# AST2002.net
KiCad netlist of a schematic drawn in EAGLE
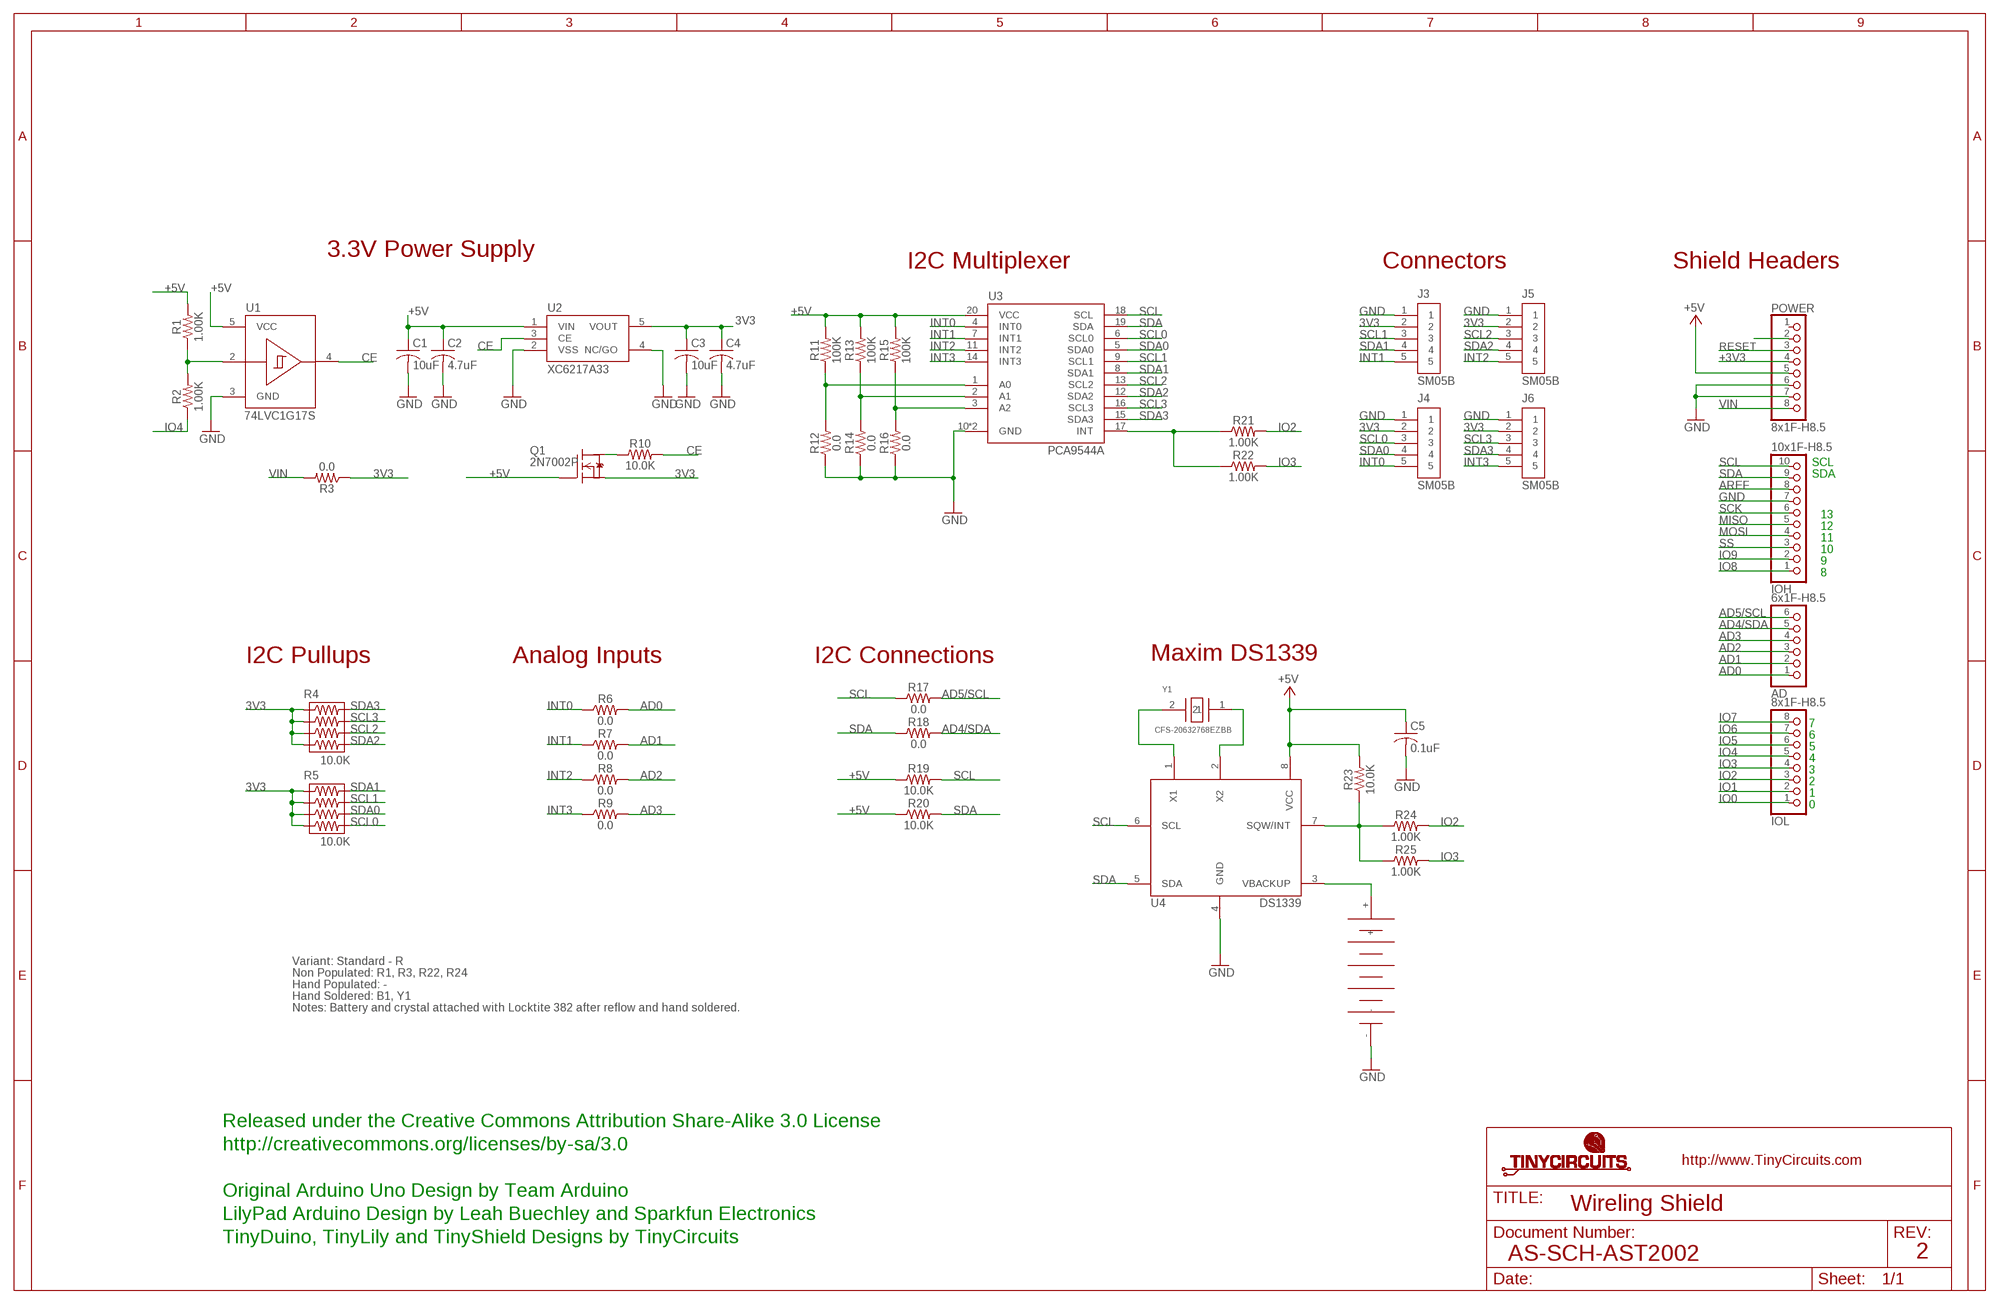
[diagram p0: schematic, sheet 1]

(export (version "E")
  (design (tool "Eeschema 10.0.6"))
  (components
    (comp (ref "AD")
      (value "6x1F-H8.5")
      (footprint "eagle-import:1X06")
      (libsource (lib "eagle-import") (part "PINHD-1X6"))
    )
    (comp (ref "B1")
      (value "ML-920S/DN")
      (footprint "eagle-import:ML-920S_DN")
      (fields (field (name "PARTNO") "AS-ITM-00182"))
      (libsource (lib "eagle-import") (part "AS-ITM-00182"))
    )
    (comp (ref "C1")
      (value "10uF")
      (footprint "eagle-import:C0603")
      (fields (field (name "PARTNO") "AS-ITM-00002") (field (name "PARTNO_1") "AS-ITM-00002"))
      (libsource (lib "eagle-import") (part "AS-ITM-00002"))
    )
    (comp (ref "C2")
      (value "4.7uF")
      (footprint "eagle-import:C0402")
      (fields (field (name "PARTNO") "AS-ITM-00242") (field (name "PARTNO_1") "AS-ITM-00242"))
      (libsource (lib "eagle-import") (part "AS-ITM-00242"))
    )
    (comp (ref "C3")
      (value "10uF")
      (footprint "eagle-import:C0603")
      (fields (field (name "PARTNO") "AS-ITM-00002"))
      (libsource (lib "eagle-import") (part "AS-ITM-00002"))
    )
    (comp (ref "C4")
      (value "4.7uF")
      (footprint "eagle-import:C0402")
      (fields (field (name "PARTNO") "AS-ITM-00242") (field (name "PARTNO_1") "AS-ITM-00242"))
      (libsource (lib "eagle-import") (part "AS-ITM-00242"))
    )
    (comp (ref "C5")
      (value "0.1uF")
      (footprint "eagle-import:C0402")
      (fields (field (name "PARTNO") "AS-ITM-00008"))
      (libsource (lib "eagle-import") (part "AS-ITM-00008"))
    )
    (comp (ref "IOH")
      (value "10x1F-H8.5")
      (footprint "eagle-import:1X10")
      (libsource (lib "eagle-import") (part "PINHD-1X10_ARD"))
    )
    (comp (ref "IOL")
      (value "8x1F-H8.5")
      (footprint "eagle-import:1X08")
      (libsource (lib "eagle-import") (part "PINHD-1X8"))
    )
    (comp (ref "J3")
      (value "SM05B")
      (footprint "eagle-import:JST_SH_5X1")
      (fields (field (name "PARTNO") "AS-ITM-00340"))
      (libsource (lib "eagle-import") (part "AS-ITM-00340"))
    )
    (comp (ref "J4")
      (value "SM05B")
      (footprint "eagle-import:JST_SH_5X1")
      (fields (field (name "PARTNO") "AS-ITM-00340"))
      (libsource (lib "eagle-import") (part "AS-ITM-00340"))
    )
    (comp (ref "J5")
      (value "SM05B")
      (footprint "eagle-import:JST_SH_5X1")
      (fields (field (name "PARTNO") "AS-ITM-00340"))
      (libsource (lib "eagle-import") (part "AS-ITM-00340"))
    )
    (comp (ref "J6")
      (value "SM05B")
      (footprint "eagle-import:JST_SH_5X1")
      (fields (field (name "PARTNO") "AS-ITM-00340"))
      (libsource (lib "eagle-import") (part "AS-ITM-00340"))
    )
    (comp (ref "POWER")
      (value "8x1F-H8.5")
      (footprint "eagle-import:1X08")
      (libsource (lib "eagle-import") (part "PINHD-1X8"))
    )
    (comp (ref "Q1")
      (value "2N7002P")
      (footprint "eagle-import:SOT-416")
      (fields (field (name "PARTNO") "AS-ITM-00110") (field (name "PARTNO_1") "AS-ITM-00110"))
      (libsource (lib "eagle-import") (part "AS-ITM-00110"))
    )
    (comp (ref "R1")
      (value "1.00K")
      (footprint "eagle-import:0402")
      (fields (field (name "PARTNO") "AS-ITM-00003") (field (name "PARTNO_1") "AS-ITM-00003"))
      (libsource (lib "eagle-import") (part "AS-ITM-00003"))
    )
    (comp (ref "R2")
      (value "1.00K")
      (footprint "eagle-import:0402")
      (fields (field (name "PARTNO") "AS-ITM-00003") (field (name "PARTNO_1") "AS-ITM-00003"))
      (libsource (lib "eagle-import") (part "AS-ITM-00003"))
    )
    (comp (ref "R3")
      (value "0.0")
      (footprint "eagle-import:0402")
      (fields (field (name "PARTNO") "AS-ITM-00076") (field (name "PARTNO_1") "AS-ITM-00076"))
      (libsource (lib "eagle-import") (part "AS-ITM-00076"))
    )
    (comp (ref "R4")
      (value "10.0K")
      (footprint "eagle-import:0402RPACK")
      (fields (field (name "PARTNO") "AS-ITM-00520") (field (name "PARTNO_1") "AS-ITM-00520"))
      (libsource (lib "eagle-import") (part "AS-ITM-00520"))
    )
    (comp (ref "R5")
      (value "10.0K")
      (footprint "eagle-import:0402RPACK")
      (fields (field (name "PARTNO") "AS-ITM-00520") (field (name "PARTNO_1") "AS-ITM-00520"))
      (libsource (lib "eagle-import") (part "AS-ITM-00520"))
    )
    (comp (ref "R6")
      (value "0.0")
      (footprint "eagle-import:0402")
      (fields (field (name "PARTNO") "AS-ITM-00076"))
      (libsource (lib "eagle-import") (part "AS-ITM-00076"))
    )
    (comp (ref "R7")
      (value "0.0")
      (footprint "eagle-import:0402")
      (fields (field (name "PARTNO") "AS-ITM-00076"))
      (libsource (lib "eagle-import") (part "AS-ITM-00076"))
    )
    (comp (ref "R8")
      (value "0.0")
      (footprint "eagle-import:0402")
      (fields (field (name "PARTNO") "AS-ITM-00076"))
      (libsource (lib "eagle-import") (part "AS-ITM-00076"))
    )
    (comp (ref "R9")
      (value "0.0")
      (footprint "eagle-import:0402")
      (fields (field (name "PARTNO") "AS-ITM-00076"))
      (libsource (lib "eagle-import") (part "AS-ITM-00076"))
    )
    (comp (ref "R10")
      (value "10.0K")
      (footprint "eagle-import:0402")
      (fields (field (name "PARTNO") "AS-ITM-00032") (field (name "PARTNO_1") "AS-ITM-00032"))
      (libsource (lib "eagle-import") (part "AS-ITM-00032"))
    )
    (comp (ref "R11")
      (value "100K")
      (footprint "eagle-import:0402")
      (fields (field (name "PARTNO") "AS-ITM-00004") (field (name "PARTNO_1") "AS-ITM-00004"))
      (libsource (lib "eagle-import") (part "AS-ITM-00004"))
    )
    (comp (ref "R12")
      (value "0.0")
      (footprint "eagle-import:0402")
      (fields (field (name "PARTNO") "AS-ITM-00076") (field (name "PARTNO_1") "AS-ITM-00076"))
      (libsource (lib "eagle-import") (part "AS-ITM-00076"))
    )
    (comp (ref "R13")
      (value "100K")
      (footprint "eagle-import:0402")
      (fields (field (name "PARTNO") "AS-ITM-00004") (field (name "PARTNO_1") "AS-ITM-00004"))
      (libsource (lib "eagle-import") (part "AS-ITM-00004"))
    )
    (comp (ref "R14")
      (value "0.0")
      (footprint "eagle-import:0402")
      (fields (field (name "PARTNO") "AS-ITM-00076") (field (name "PARTNO_1") "AS-ITM-00076"))
      (libsource (lib "eagle-import") (part "AS-ITM-00076"))
    )
    (comp (ref "R15")
      (value "100K")
      (footprint "eagle-import:0402")
      (fields (field (name "PARTNO") "AS-ITM-00004") (field (name "PARTNO_1") "AS-ITM-00004"))
      (libsource (lib "eagle-import") (part "AS-ITM-00004"))
    )
    (comp (ref "R16")
      (value "0.0")
      (footprint "eagle-import:0402")
      (fields (field (name "PARTNO") "AS-ITM-00076") (field (name "PARTNO_1") "AS-ITM-00076"))
      (libsource (lib "eagle-import") (part "AS-ITM-00076"))
    )
    (comp (ref "R17")
      (value "0.0")
      (footprint "eagle-import:0402")
      (fields (field (name "PARTNO") "AS-ITM-00076"))
      (libsource (lib "eagle-import") (part "AS-ITM-00076"))
    )
    (comp (ref "R18")
      (value "0.0")
      (footprint "eagle-import:0402")
      (fields (field (name "PARTNO") "AS-ITM-00076"))
      (libsource (lib "eagle-import") (part "AS-ITM-00076"))
    )
    (comp (ref "R19")
      (value "10.0K")
      (footprint "eagle-import:0402")
      (fields (field (name "PARTNO") "AS-ITM-00032"))
      (libsource (lib "eagle-import") (part "AS-ITM-00032"))
    )
    (comp (ref "R20")
      (value "10.0K")
      (footprint "eagle-import:0402")
      (fields (field (name "PARTNO") "AS-ITM-00032"))
      (libsource (lib "eagle-import") (part "AS-ITM-00032"))
    )
    (comp (ref "R21")
      (value "1.00K")
      (footprint "eagle-import:0402")
      (fields (field (name "PARTNO") "AS-ITM-00003"))
      (libsource (lib "eagle-import") (part "AS-ITM-00003"))
    )
    (comp (ref "R22")
      (value "1.00K")
      (footprint "eagle-import:0402")
      (fields (field (name "PARTNO") "AS-ITM-00003"))
      (libsource (lib "eagle-import") (part "AS-ITM-00003"))
    )
    (comp (ref "R23")
      (value "10.0K")
      (footprint "eagle-import:0402")
      (fields (field (name "PARTNO") "AS-ITM-00032") (field (name "PARTNO_1") "AS-ITM-00032"))
      (libsource (lib "eagle-import") (part "AS-ITM-00032"))
    )
    (comp (ref "R24")
      (value "1.00K")
      (footprint "eagle-import:0402")
      (fields (field (name "PARTNO") "AS-ITM-00003") (field (name "PARTNO_1") "AS-ITM-00003"))
      (libsource (lib "eagle-import") (part "AS-ITM-00003"))
    )
    (comp (ref "R25")
      (value "1.00K")
      (footprint "eagle-import:0402")
      (fields (field (name "PARTNO") "AS-ITM-00003") (field (name "PARTNO_1") "AS-ITM-00003"))
      (libsource (lib "eagle-import") (part "AS-ITM-00003"))
    )
    (comp (ref "U1")
      (value "74LVC1G17S")
      (footprint "eagle-import:SOT-353")
      (fields (field (name "PARTNO") "AS-ITM-00382"))
      (libsource (lib "eagle-import") (part "AS-ITM-00382"))
    )
    (comp (ref "U2")
      (value "XC6217A33")
      (footprint "eagle-import:SOT-25")
      (fields (field (name "PARTNO") "AS-ITM-00249") (field (name "PARTNO_1") "AS-ITM-00249"))
      (libsource (lib "eagle-import") (part "AS-ITM-00249"))
    )
    (comp (ref "U3")
      (value "PCA9544A")
      (footprint "eagle-import:VQFN-20_4.5X3.5")
      (fields (field (name "PARTNO") "AS-ITM-00342"))
      (libsource (lib "eagle-import") (part "AS-ITM-00342"))
    )
    (comp (ref "U4")
      (value "DS1339")
      (footprint "eagle-import:8-USOP")
      (fields (field (name "PARTNO") "AS-ITM-00181"))
      (libsource (lib "eagle-import") (part "AS-ITM-00181"))
    )
    (comp (ref "Y1")
      (value "CFS-20632768EZBB")
      (footprint "eagle-import:CRYSTAL_1.9MM_TH")
      (fields (field (name "PARTNO") "AS-ITM-00348"))
      (libsource (lib "eagle-import") (part "AS-ITM-00348"))
    )
  )
  (nets
    (net (code "1") (name "+5V") (class "Default")
      (node (ref "C1") (pin "1") (pinfunction "1_1") (pintype "passive"))
      (node (ref "C2") (pin "1") (pinfunction "1_1") (pintype "passive"))
      (node (ref "C5") (pin "1") (pinfunction "1_1") (pintype "passive"))
      (node (ref "POWER") (pin "5") (pinfunction "5_5") (pintype "passive"))
      (node (ref "Q1") (pin "1") (pinfunction "G_1") (pintype "passive"))
      (node (ref "R1") (pin "2") (pinfunction "2_2") (pintype "passive"))
      (node (ref "R11") (pin "2") (pinfunction "2_2") (pintype "passive"))
      (node (ref "R13") (pin "2") (pinfunction "2_2") (pintype "passive"))
      (node (ref "R15") (pin "2") (pinfunction "2_2") (pintype "passive"))
      (node (ref "R19") (pin "1") (pinfunction "1_1") (pintype "passive"))
      (node (ref "R20") (pin "1") (pinfunction "1_1") (pintype "passive"))
      (node (ref "R23") (pin "2") (pinfunction "2_2") (pintype "passive"))
      (node (ref "U1") (pin "5") (pinfunction "VCC_5") (pintype "bidirectional"))
      (node (ref "U2") (pin "1") (pinfunction "VIN_1") (pintype "bidirectional"))
      (node (ref "U3") (pin "20") (pinfunction "VCC_20") (pintype "bidirectional"))
      (node (ref "U4") (pin "8") (pinfunction "VCC_8") (pintype "bidirectional"))
    )
    (net (code "2") (name "/+3V3") (class "Default")
      (node (ref "POWER") (pin "4") (pinfunction "4_4") (pintype "passive"))
    )
    (net (code "3") (name "/3V3") (class "Default")
      (node (ref "C3") (pin "1") (pinfunction "1_1") (pintype "passive"))
      (node (ref "C4") (pin "1") (pinfunction "1_1") (pintype "passive"))
      (node (ref "J3") (pin "2") (pinfunction "2_2") (pintype "bidirectional"))
      (node (ref "J4") (pin "2") (pinfunction "2_2") (pintype "bidirectional"))
      (node (ref "J5") (pin "2") (pinfunction "2_2") (pintype "bidirectional"))
      (node (ref "J6") (pin "2") (pinfunction "2_2") (pintype "bidirectional"))
      (node (ref "Q1") (pin "2") (pinfunction "S_2") (pintype "passive"))
      (node (ref "R3") (pin "1") (pinfunction "1_1") (pintype "passive"))
      (node (ref "R4") (pin "1") (pinfunction "1_1") (pintype "passive"))
      (node (ref "R4") (pin "3") (pinfunction "3_3") (pintype "passive"))
      (node (ref "R4") (pin "5") (pinfunction "5_5") (pintype "passive"))
      (node (ref "R4") (pin "7") (pinfunction "7_7") (pintype "passive"))
      (node (ref "R5") (pin "1") (pinfunction "1_1") (pintype "passive"))
      (node (ref "R5") (pin "3") (pinfunction "3_3") (pintype "passive"))
      (node (ref "R5") (pin "5") (pinfunction "5_5") (pintype "passive"))
      (node (ref "R5") (pin "7") (pinfunction "7_7") (pintype "passive"))
      (node (ref "U2") (pin "5") (pinfunction "VOUT_5") (pintype "bidirectional"))
    )
    (net (code "4") (name "/AD0") (class "Default")
      (node (ref "AD") (pin "1") (pinfunction "1_1") (pintype "passive"))
      (node (ref "R6") (pin "2") (pinfunction "2_2") (pintype "passive"))
    )
    (net (code "5") (name "/AD1") (class "Default")
      (node (ref "AD") (pin "2") (pinfunction "2_2") (pintype "passive"))
      (node (ref "R7") (pin "2") (pinfunction "2_2") (pintype "passive"))
    )
    (net (code "6") (name "/AD2") (class "Default")
      (node (ref "AD") (pin "3") (pinfunction "3_3") (pintype "passive"))
      (node (ref "R8") (pin "2") (pinfunction "2_2") (pintype "passive"))
    )
    (net (code "7") (name "/AD3") (class "Default")
      (node (ref "AD") (pin "4") (pinfunction "4_4") (pintype "passive"))
      (node (ref "R9") (pin "2") (pinfunction "2_2") (pintype "passive"))
    )
    (net (code "8") (name "/AD4{slash}SDA") (class "Default")
      (node (ref "AD") (pin "5") (pinfunction "5_5") (pintype "passive"))
      (node (ref "R18") (pin "2") (pinfunction "2_2") (pintype "passive"))
    )
    (net (code "9") (name "/AD5{slash}SCL") (class "Default")
      (node (ref "AD") (pin "6") (pinfunction "6_6") (pintype "passive"))
      (node (ref "R17") (pin "2") (pinfunction "2_2") (pintype "passive"))
    )
    (net (code "10") (name "/AREF") (class "Default")
      (node (ref "IOH") (pin "8") (pinfunction "8_8") (pintype "passive"))
    )
    (net (code "11") (name "/CE") (class "Default")
      (node (ref "R10") (pin "2") (pinfunction "2_2") (pintype "passive"))
      (node (ref "U1") (pin "4") (pinfunction "Y_4") (pintype "bidirectional"))
      (node (ref "U2") (pin "3") (pinfunction "CE_3") (pintype "bidirectional"))
    )
    (net (code "12") (name "/INT0") (class "Default")
      (node (ref "J4") (pin "5") (pinfunction "5_5") (pintype "bidirectional"))
      (node (ref "R6") (pin "1") (pinfunction "1_1") (pintype "passive"))
      (node (ref "U3") (pin "4") (pinfunction "INT0_4") (pintype "bidirectional"))
    )
    (net (code "13") (name "/INT1") (class "Default")
      (node (ref "J3") (pin "5") (pinfunction "5_5") (pintype "bidirectional"))
      (node (ref "R7") (pin "1") (pinfunction "1_1") (pintype "passive"))
      (node (ref "U3") (pin "7") (pinfunction "INT1_7") (pintype "bidirectional"))
    )
    (net (code "14") (name "/INT2") (class "Default")
      (node (ref "J5") (pin "5") (pinfunction "5_5") (pintype "bidirectional"))
      (node (ref "R8") (pin "1") (pinfunction "1_1") (pintype "passive"))
      (node (ref "U3") (pin "11") (pinfunction "INT2_11") (pintype "bidirectional"))
    )
    (net (code "15") (name "/INT3") (class "Default")
      (node (ref "J6") (pin "5") (pinfunction "5_5") (pintype "bidirectional"))
      (node (ref "R9") (pin "1") (pinfunction "1_1") (pintype "passive"))
      (node (ref "U3") (pin "14") (pinfunction "INT3_14") (pintype "bidirectional"))
    )
    (net (code "16") (name "/IO0") (class "Default")
      (node (ref "IOL") (pin "1") (pinfunction "1_1") (pintype "passive"))
    )
    (net (code "17") (name "/IO1") (class "Default")
      (node (ref "IOL") (pin "2") (pinfunction "2_2") (pintype "passive"))
    )
    (net (code "18") (name "/IO2") (class "Default")
      (node (ref "IOL") (pin "3") (pinfunction "3_3") (pintype "passive"))
      (node (ref "R21") (pin "2") (pinfunction "2_2") (pintype "passive"))
      (node (ref "R24") (pin "2") (pinfunction "2_2") (pintype "passive"))
    )
    (net (code "19") (name "/IO3") (class "Default")
      (node (ref "IOL") (pin "4") (pinfunction "4_4") (pintype "passive"))
      (node (ref "R22") (pin "2") (pinfunction "2_2") (pintype "passive"))
      (node (ref "R25") (pin "2") (pinfunction "2_2") (pintype "passive"))
    )
    (net (code "20") (name "/IO4") (class "Default")
      (node (ref "IOL") (pin "5") (pinfunction "5_5") (pintype "passive"))
      (node (ref "R2") (pin "1") (pinfunction "1_1") (pintype "passive"))
    )
    (net (code "21") (name "/IO5") (class "Default")
      (node (ref "IOL") (pin "6") (pinfunction "6_6") (pintype "passive"))
    )
    (net (code "22") (name "/IO6") (class "Default")
      (node (ref "IOL") (pin "7") (pinfunction "7_7") (pintype "passive"))
    )
    (net (code "23") (name "/IO7") (class "Default")
      (node (ref "IOL") (pin "8") (pinfunction "8_8") (pintype "passive"))
    )
    (net (code "24") (name "/IO8") (class "Default")
      (node (ref "IOH") (pin "1") (pinfunction "1_1") (pintype "passive"))
    )
    (net (code "25") (name "/IO9") (class "Default")
      (node (ref "IOH") (pin "2") (pinfunction "2_2") (pintype "passive"))
    )
    (net (code "26") (name "/MISO") (class "Default")
      (node (ref "IOH") (pin "5") (pinfunction "5_5") (pintype "passive"))
    )
    (net (code "27") (name "/MOSI") (class "Default")
      (node (ref "IOH") (pin "4") (pinfunction "4_4") (pintype "passive"))
    )
    (net (code "28") (name "/RESET") (class "Default")
      (node (ref "POWER") (pin "3") (pinfunction "3_3") (pintype "passive"))
    )
    (net (code "29") (name "/SCK") (class "Default")
      (node (ref "IOH") (pin "6") (pinfunction "6_6") (pintype "passive"))
    )
    (net (code "30") (name "/SCL") (class "Default")
      (node (ref "IOH") (pin "10") (pinfunction "10_10") (pintype "passive"))
      (node (ref "R17") (pin "1") (pinfunction "1_1") (pintype "passive"))
      (node (ref "R19") (pin "2") (pinfunction "2_2") (pintype "passive"))
      (node (ref "U3") (pin "18") (pinfunction "SCL_18") (pintype "bidirectional"))
      (node (ref "U4") (pin "6") (pinfunction "SCL_6") (pintype "bidirectional"))
    )
    (net (code "31") (name "/SCL0") (class "Default")
      (node (ref "J4") (pin "3") (pinfunction "3_3") (pintype "bidirectional"))
      (node (ref "R5") (pin "8") (pinfunction "8_8") (pintype "passive"))
      (node (ref "U3") (pin "6") (pinfunction "SCL0_6") (pintype "bidirectional"))
    )
    (net (code "32") (name "/SCL1") (class "Default")
      (node (ref "J3") (pin "3") (pinfunction "3_3") (pintype "bidirectional"))
      (node (ref "R5") (pin "4") (pinfunction "4_4") (pintype "passive"))
      (node (ref "U3") (pin "9") (pinfunction "SCL1_9") (pintype "bidirectional"))
    )
    (net (code "33") (name "/SCL2") (class "Default")
      (node (ref "J5") (pin "3") (pinfunction "3_3") (pintype "bidirectional"))
      (node (ref "R4") (pin "6") (pinfunction "6_6") (pintype "passive"))
      (node (ref "U3") (pin "13") (pinfunction "SCL2_13") (pintype "bidirectional"))
    )
    (net (code "34") (name "/SCL3") (class "Default")
      (node (ref "J6") (pin "3") (pinfunction "3_3") (pintype "bidirectional"))
      (node (ref "R4") (pin "4") (pinfunction "4_4") (pintype "passive"))
      (node (ref "U3") (pin "16") (pinfunction "SCL3_16") (pintype "bidirectional"))
    )
    (net (code "35") (name "/SDA") (class "Default")
      (node (ref "IOH") (pin "9") (pinfunction "9_9") (pintype "passive"))
      (node (ref "R18") (pin "1") (pinfunction "1_1") (pintype "passive"))
      (node (ref "R20") (pin "2") (pinfunction "2_2") (pintype "passive"))
      (node (ref "U3") (pin "19") (pinfunction "SDA_19") (pintype "bidirectional"))
      (node (ref "U4") (pin "5") (pinfunction "SDA_5") (pintype "bidirectional"))
    )
    (net (code "36") (name "/SDA0") (class "Default")
      (node (ref "J4") (pin "4") (pinfunction "4_4") (pintype "bidirectional"))
      (node (ref "R5") (pin "6") (pinfunction "6_6") (pintype "passive"))
      (node (ref "U3") (pin "5") (pinfunction "SDA0_5") (pintype "bidirectional"))
    )
    (net (code "37") (name "/SDA1") (class "Default")
      (node (ref "J3") (pin "4") (pinfunction "4_4") (pintype "bidirectional"))
      (node (ref "R5") (pin "2") (pinfunction "2_2") (pintype "passive"))
      (node (ref "U3") (pin "8") (pinfunction "SDA1_8") (pintype "bidirectional"))
    )
    (net (code "38") (name "/SDA2") (class "Default")
      (node (ref "J5") (pin "4") (pinfunction "4_4") (pintype "bidirectional"))
      (node (ref "R4") (pin "8") (pinfunction "8_8") (pintype "passive"))
      (node (ref "U3") (pin "12") (pinfunction "SDA2_12") (pintype "bidirectional"))
    )
    (net (code "39") (name "/SDA3") (class "Default")
      (node (ref "J6") (pin "4") (pinfunction "4_4") (pintype "bidirectional"))
      (node (ref "R4") (pin "2") (pinfunction "2_2") (pintype "passive"))
      (node (ref "U3") (pin "15") (pinfunction "SDA3_15") (pintype "bidirectional"))
    )
    (net (code "40") (name "/SS") (class "Default")
      (node (ref "IOH") (pin "3") (pinfunction "3_3") (pintype "passive"))
    )
    (net (code "41") (name "/VIN") (class "Default")
      (node (ref "POWER") (pin "8") (pinfunction "8_8") (pintype "passive"))
      (node (ref "R3") (pin "2") (pinfunction "2_2") (pintype "passive"))
    )
    (net (code "42") (name "GND") (class "Default")
      (node (ref "B1") (pin "-") (pinfunction "-_-") (pintype "bidirectional"))
      (node (ref "C1") (pin "2") (pinfunction "2_2") (pintype "passive"))
      (node (ref "C2") (pin "2") (pinfunction "2_2") (pintype "passive"))
      (node (ref "C3") (pin "2") (pinfunction "2_2") (pintype "passive"))
      (node (ref "C4") (pin "2") (pinfunction "2_2") (pintype "passive"))
      (node (ref "C5") (pin "2") (pinfunction "2_2") (pintype "passive"))
      (node (ref "IOH") (pin "7") (pinfunction "7_7") (pintype "passive"))
      (node (ref "J3") (pin "1") (pinfunction "1_1") (pintype "bidirectional"))
      (node (ref "J4") (pin "1") (pinfunction "1_1") (pintype "bidirectional"))
      (node (ref "J5") (pin "1") (pinfunction "1_1") (pintype "bidirectional"))
      (node (ref "J6") (pin "1") (pinfunction "1_1") (pintype "bidirectional"))
      (node (ref "POWER") (pin "6") (pinfunction "6_6") (pintype "passive"))
      (node (ref "POWER") (pin "7") (pinfunction "7_7") (pintype "passive"))
      (node (ref "R12") (pin "1") (pinfunction "1_1") (pintype "passive"))
      (node (ref "R14") (pin "1") (pinfunction "1_1") (pintype "passive"))
      (node (ref "R16") (pin "1") (pinfunction "1_1") (pintype "passive"))
      (node (ref "U1") (pin "3") (pinfunction "GND_3") (pintype "bidirectional"))
      (node (ref "U2") (pin "2") (pinfunction "VSS_2") (pintype "power_in"))
      (node (ref "U2") (pin "4") (pinfunction "NC/GO_4") (pintype "bidirectional"))
      (node (ref "U3") (pin "10") (pinfunction "GND_10") (pintype "bidirectional"))
      (node (ref "U3") (pin "PAD") (pinfunction "GND_PAD") (pintype "bidirectional"))
      (node (ref "U4") (pin "4") (pinfunction "GND_4") (pintype "bidirectional"))
    )
    (net (code "43") (name "Net-(Q1-D)") (class "Default")
      (node (ref "Q1") (pin "3") (pinfunction "D_3") (pintype "passive"))
      (node (ref "R10") (pin "1") (pinfunction "1_1") (pintype "passive"))
    )
    (net (code "44") (name "Net-(U1-A)") (class "Default")
      (node (ref "R1") (pin "1") (pinfunction "1_1") (pintype "passive"))
      (node (ref "R2") (pin "2") (pinfunction "2_2") (pintype "passive"))
      (node (ref "U1") (pin "2") (pinfunction "A_2") (pintype "bidirectional"))
    )
    (net (code "45") (name "Net-(U3-A0)") (class "Default")
      (node (ref "R11") (pin "1") (pinfunction "1_1") (pintype "passive"))
      (node (ref "R12") (pin "2") (pinfunction "2_2") (pintype "passive"))
      (node (ref "U3") (pin "1") (pinfunction "A0_1") (pintype "bidirectional"))
    )
    (net (code "46") (name "Net-(U3-A1)") (class "Default")
      (node (ref "R13") (pin "1") (pinfunction "1_1") (pintype "passive"))
      (node (ref "R14") (pin "2") (pinfunction "2_2") (pintype "passive"))
      (node (ref "U3") (pin "2") (pinfunction "A1_2") (pintype "bidirectional"))
    )
    (net (code "47") (name "Net-(U3-A2)") (class "Default")
      (node (ref "R15") (pin "1") (pinfunction "1_1") (pintype "passive"))
      (node (ref "R16") (pin "2") (pinfunction "2_2") (pintype "passive"))
      (node (ref "U3") (pin "3") (pinfunction "A2_3") (pintype "bidirectional"))
    )
    (net (code "48") (name "Net-(U3-INT)") (class "Default")
      (node (ref "R21") (pin "1") (pinfunction "1_1") (pintype "passive"))
      (node (ref "R22") (pin "1") (pinfunction "1_1") (pintype "passive"))
      (node (ref "U3") (pin "17") (pinfunction "INT_17") (pintype "bidirectional"))
    )
    (net (code "49") (name "Net-(U4-SQW{slash}INT)") (class "Default")
      (node (ref "R23") (pin "1") (pinfunction "1_1") (pintype "passive"))
      (node (ref "R24") (pin "1") (pinfunction "1_1") (pintype "passive"))
      (node (ref "R25") (pin "1") (pinfunction "1_1") (pintype "passive"))
      (node (ref "U4") (pin "7") (pinfunction "SQW/INT_7") (pintype "bidirectional"))
    )
    (net (code "50") (name "Net-(U4-VBACKUP)") (class "Default")
      (node (ref "B1") (pin "+") (pinfunction "+_+") (pintype "bidirectional"))
      (node (ref "U4") (pin "3") (pinfunction "VBACKUP_3") (pintype "bidirectional"))
    )
    (net (code "51") (name "Net-(U4-X1)") (class "Default")
      (node (ref "U4") (pin "1") (pinfunction "X1_1") (pintype "bidirectional"))
      (node (ref "Y1") (pin "2") (pinfunction "1_2") (pintype "bidirectional"))
    )
    (net (code "52") (name "Net-(U4-X2)") (class "Default")
      (node (ref "U4") (pin "2") (pinfunction "X2_2") (pintype "bidirectional"))
      (node (ref "Y1") (pin "1") (pinfunction "2_1") (pintype "bidirectional"))
    )
    (net (code "53") (name "unconnected-(POWER-Pad1)") (class "Default")
      (node (ref "POWER") (pin "1") (pinfunction "1_1") (pintype "passive"))
    )
    (net (code "54") (name "unconnected-(POWER-Pad2)") (class "Default")
      (node (ref "POWER") (pin "2") (pinfunction "2_2") (pintype "passive"))
    )
  )
)
